# 407-power.net
KiCad netlist of a schematic drawn in Altium Designer
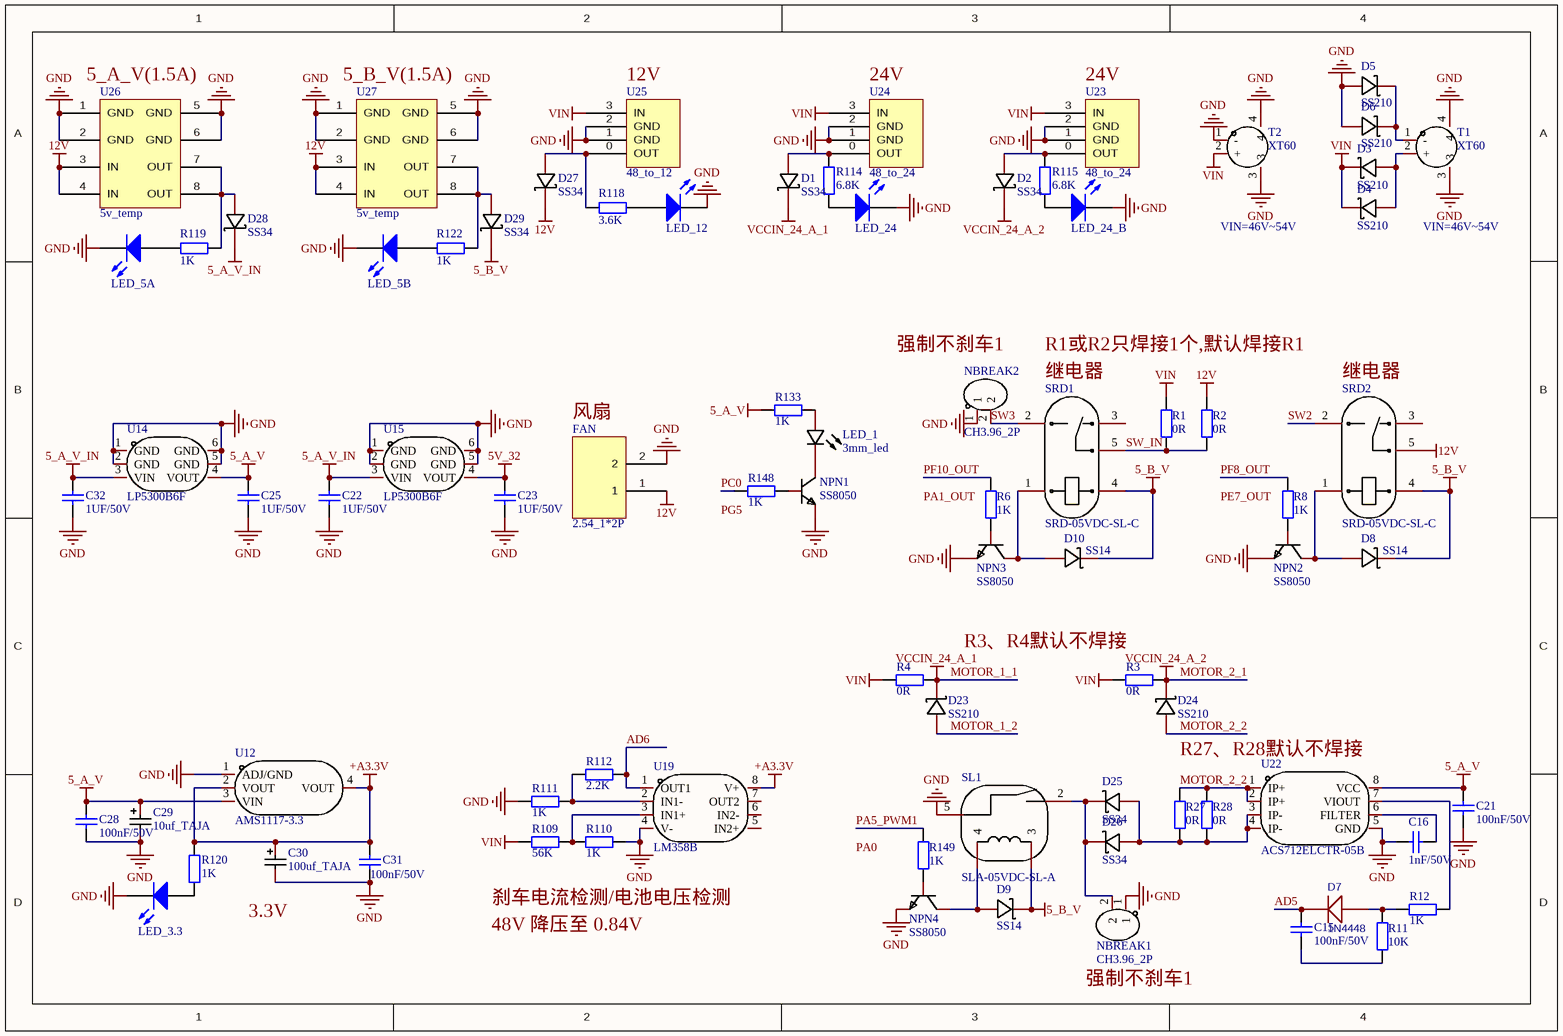
[diagram p0: 407-power.schdoc]

(export (version "E")
  (design (tool "Eeschema 10.0.6"))
  (components
    (comp (ref "C15")
      (value "100nF/50V")
      (description "Capacitor")
      (fields (field (name "PUBLISHER") "Altium Limited"))
      (libsource (lib "Miscellaneous Devices") (part "Cap"))
    )
    (comp (ref "C16")
      (value "1nF/50V")
      (description "Capacitor")
      (fields (field (name "PUBLISHER") "Altium Limited"))
      (libsource (lib "Miscellaneous Devices") (part "Cap"))
    )
    (comp (ref "C21")
      (value "100nF/50V")
      (description "Capacitor")
      (fields (field (name "PUBLISHER") "Altium Limited"))
      (libsource (lib "Miscellaneous Devices") (part "Cap"))
    )
    (comp (ref "C22")
      (value "1UF/50V")
      (description "Capacitor")
      (fields (field (name "PUBLISHER") "Altium Limited"))
      (libsource (lib "Miscellaneous Devices") (part "Cap"))
    )
    (comp (ref "C23")
      (value "1UF/50V")
      (description "Capacitor")
      (fields (field (name "PUBLISHER") "Altium Limited"))
      (libsource (lib "Miscellaneous Devices") (part "Cap"))
    )
    (comp (ref "C25")
      (value "1UF/50V")
      (description "Capacitor")
      (fields (field (name "PUBLISHER") "Altium Limited"))
      (libsource (lib "Miscellaneous Devices") (part "Cap"))
    )
    (comp (ref "C28")
      (value "100nF/50V")
      (description "Capacitor")
      (fields (field (name "PUBLISHER") "Altium Limited"))
      (libsource (lib "Miscellaneous Devices") (part "Cap"))
    )
    (comp (ref "C29")
      (value "10uf_TAJA")
      (footprint "10uf_TAJA")
      (libsource (lib "tianjin_2023") (part "10uf_TAJA"))
    )
    (comp (ref "C30")
      (value "100uf_TAJA")
      (footprint "100uf_TAJA")
      (libsource (lib "tianjin_2023") (part "100uf_TAJA"))
    )
    (comp (ref "C31")
      (value "100nF/50V")
      (description "Capacitor")
      (fields (field (name "PUBLISHER") "Altium Limited"))
      (libsource (lib "Miscellaneous Devices") (part "Cap"))
    )
    (comp (ref "C32")
      (value "1UF/50V")
      (description "Capacitor")
      (fields (field (name "PUBLISHER") "Altium Limited"))
      (libsource (lib "Miscellaneous Devices") (part "Cap"))
    )
    (comp (ref "D1") (value "SS34") (footprint "SS34") (libsource (lib "tianjin_2023") (part "SS34")))
    (comp (ref "D2") (value "SS34") (footprint "SS34") (libsource (lib "tianjin_2023") (part "SS34")))
    (comp (ref "D3") (value "SS210") (footprint "SS210") (libsource (lib "tianjin_2023") (part "SS210")))
    (comp (ref "D4") (value "SS210") (footprint "SS210") (libsource (lib "tianjin_2023") (part "SS210")))
    (comp (ref "D5") (value "SS210") (footprint "SS210") (libsource (lib "tianjin_2023") (part "SS210")))
    (comp (ref "D6") (value "SS210") (footprint "SS210") (libsource (lib "tianjin_2023") (part "SS210")))
    (comp (ref "D7")
      (value "1N4448")
      (fields (field (name "MANUFACTURER") "Diodes Inc") (field (name "MANUFACTURER PART") "1N4448HLP-7"))
      (libsource (lib "altium-import") (part "root_1_1N4448_"))
    )
    (comp (ref "D8") (value "SS14") (footprint "SS14") (libsource (lib "tianjin_2023") (part "SS14")))
    (comp (ref "D9") (value "SS14") (footprint "SS14") (libsource (lib "tianjin_2023") (part "SS14")))
    (comp (ref "D10") (value "SS14") (footprint "SS14") (libsource (lib "tianjin_2023") (part "SS14")))
    (comp (ref "D23") (value "SS210") (footprint "SS210") (libsource (lib "tianjin_2023") (part "SS210")))
    (comp (ref "D24") (value "SS210") (footprint "SS210") (libsource (lib "tianjin_2023") (part "SS210")))
    (comp (ref "D25") (value "SS34") (footprint "SS34") (libsource (lib "tianjin_2023") (part "SS34")))
    (comp (ref "D26") (value "SS34") (footprint "SS34") (libsource (lib "tianjin_2023") (part "SS34")))
    (comp (ref "D27") (value "SS34") (footprint "SS34") (libsource (lib "tianjin_2023") (part "SS34")))
    (comp (ref "D28") (value "SS34") (footprint "SS34") (libsource (lib "tianjin_2023") (part "SS34")))
    (comp (ref "D29") (value "SS34") (footprint "SS34") (libsource (lib "tianjin_2023") (part "SS34")))
    (comp (ref "FAN")
      (value "2.54_1*2P")
      (footprint "2.54_1*2P")
      (libsource (lib "tianjin_2023") (part "2.54_1*2P"))
    )
    (comp (ref "LED_1")
      (value "3mm_led")
      (footprint "3mm_led")
      (libsource (lib "tianjin_2023") (part "3mm_led"))
    )
    (comp (ref "LED_3.3")
      (value "LED")
      (footprint "LED")
      (description "发光二极管")
      (libsource (lib "0.3 - LED发光二极管-IR二极管_接收管-光耦") (part "LED"))
    )
    (comp (ref "LED_5A")
      (value "LED")
      (footprint "LED")
      (description "发光二极管")
      (libsource (lib "0.3 - LED发光二极管-IR二极管_接收管-光耦") (part "LED"))
    )
    (comp (ref "LED_5B")
      (value "LED")
      (footprint "LED")
      (description "发光二极管")
      (libsource (lib "0.3 - LED发光二极管-IR二极管_接收管-光耦") (part "LED"))
    )
    (comp (ref "LED_12")
      (value "LED")
      (footprint "LED")
      (description "发光二极管")
      (libsource (lib "0.3 - LED发光二极管-IR二极管_接收管-光耦") (part "LED"))
    )
    (comp (ref "LED_24")
      (value "LED")
      (footprint "LED")
      (description "发光二极管")
      (libsource (lib "0.3 - LED发光二极管-IR二极管_接收管-光耦") (part "LED"))
    )
    (comp (ref "LED_24_B")
      (value "LED")
      (footprint "LED")
      (description "发光二极管")
      (libsource (lib "0.3 - LED发光二极管-IR二极管_接收管-光耦") (part "LED"))
    )
    (comp (ref "NBREAK1")
      (value "CH3.96_2P")
      (footprint "CH3.96_2P")
      (libsource (lib "tianjin_2023") (part "CH3.96_2P"))
    )
    (comp (ref "NBREAK2") (value "CH3.96_2P") (libsource (lib "tianjin_2023") (part "CH3.96_2P")))
    (comp (ref "NPN1") (value "SS8050") (footprint "SS8050") (libsource (lib "tianjin_2023") (part "SS8050")))
    (comp (ref "NPN2") (value "SS8050") (footprint "SS8050") (libsource (lib "tianjin_2023") (part "SS8050")))
    (comp (ref "NPN3") (value "SS8050") (footprint "SS8050") (libsource (lib "tianjin_2023") (part "SS8050")))
    (comp (ref "NPN4") (value "SS8050") (footprint "SS8050") (libsource (lib "tianjin_2023") (part "SS8050")))
    (comp (ref "R1")
      (value "0R")
      (footprint "R1206_M")
      (description "Resistor")
      (fields (field (name "PUBLISHER") "Altium Limited"))
      (libsource (lib "") (part "Res2_3"))
    )
    (comp (ref "R2")
      (value "0R")
      (footprint "R1206_M")
      (description "Resistor")
      (fields (field (name "PUBLISHER") "Altium Limited"))
      (libsource (lib "") (part "Res2_1"))
    )
    (comp (ref "R3")
      (value "0R")
      (footprint "R1206_M")
      (description "Resistor")
      (fields (field (name "PUBLISHER") "Altium Limited"))
      (libsource (lib "MOS motor driving module ") (part "Res2"))
    )
    (comp (ref "R4")
      (value "0R")
      (footprint "R1206_M")
      (description "Resistor")
      (fields (field (name "PUBLISHER") "Altium Limited"))
      (libsource (lib "MOS motor driving module ") (part "Res2"))
    )
    (comp (ref "R6")
      (value "1K")
      (description "Resistor")
      (fields (field (name "PUBLISHER") "Altium Limited"))
      (libsource (lib "") (part "Res2_1"))
    )
    (comp (ref "R8")
      (value "1K")
      (description "Resistor")
      (fields (field (name "PUBLISHER") "Altium Limited"))
      (libsource (lib "") (part "Res2_1"))
    )
    (comp (ref "R11")
      (value "10K")
      (description "Resistor")
      (fields (field (name "PUBLISHER") "Altium Limited"))
      (libsource (lib "") (part "Res2_1"))
    )
    (comp (ref "R12")
      (value "1K")
      (description "Resistor")
      (fields (field (name "PUBLISHER") "Altium Limited"))
      (libsource (lib "") (part "Res2_2"))
    )
    (comp (ref "R27")
      (value "0R")
      (footprint "R1206_M")
      (description "Resistor")
      (fields (field (name "PUBLISHER") "Altium Limited"))
      (libsource (lib "") (part "Res2_3"))
    )
    (comp (ref "R28")
      (value "0R")
      (footprint "R1206_M")
      (description "Resistor")
      (fields (field (name "PUBLISHER") "Altium Limited"))
      (libsource (lib "") (part "Res2_3"))
    )
    (comp (ref "R109")
      (value "56K")
      (footprint "R0603_L")
      (description "Resistor")
      (fields (field (name "PUBLISHER") "Altium Limited"))
      (libsource (lib "MOS motor driving module ") (part "Res2"))
    )
    (comp (ref "R110")
      (value "1K")
      (footprint "R0603_L")
      (description "Resistor")
      (fields (field (name "PUBLISHER") "Altium Limited"))
      (libsource (lib "MOS motor driving module ") (part "Res2"))
    )
    (comp (ref "R111")
      (value "1K")
      (footprint "R0603_L")
      (description "Resistor")
      (fields (field (name "PUBLISHER") "Altium Limited"))
      (libsource (lib "MOS motor driving module ") (part "Res2"))
    )
    (comp (ref "R112")
      (value "2.2K")
      (footprint "R0603_L")
      (description "Resistor")
      (fields (field (name "PUBLISHER") "Altium Limited"))
      (libsource (lib "MOS motor driving module ") (part "Res2"))
    )
    (comp (ref "R114")
      (value "6.8K")
      (description "贴片电阻")
      (libsource (lib "0.1 - 电阻-电容-电感-晶振-晶体-磁珠-电位器-法拉电容-馈通电容") (part "R"))
    )
    (comp (ref "R115")
      (value "6.8K")
      (description "贴片电阻")
      (libsource (lib "0.1 - 电阻-电容-电感-晶振-晶体-磁珠-电位器-法拉电容-馈通电容") (part "R"))
    )
    (comp (ref "R118")
      (value "3.6K")
      (description "贴片电阻")
      (libsource (lib "0.1 - 电阻-电容-电感-晶振-晶体-磁珠-电位器-法拉电容-馈通电容") (part "R"))
    )
    (comp (ref "R119")
      (value "1K")
      (description "贴片电阻")
      (libsource (lib "0.1 - 电阻-电容-电感-晶振-晶体-磁珠-电位器-法拉电容-馈通电容") (part "R"))
    )
    (comp (ref "R120")
      (value "1K")
      (description "贴片电阻")
      (libsource (lib "0.1 - 电阻-电容-电感-晶振-晶体-磁珠-电位器-法拉电容-馈通电容") (part "R"))
    )
    (comp (ref "R122")
      (value "1K")
      (description "贴片电阻")
      (libsource (lib "0.1 - 电阻-电容-电感-晶振-晶体-磁珠-电位器-法拉电容-馈通电容") (part "R"))
    )
    (comp (ref "R133")
      (value "1K")
      (description "Resistor")
      (fields (field (name "PUBLISHER") "Altium Limited"))
      (libsource (lib "MOS motor driving module ") (part "Res2"))
    )
    (comp (ref "R148")
      (value "1K")
      (description "Resistor")
      (fields (field (name "PUBLISHER") "Altium Limited"))
      (libsource (lib "") (part "Res2_2"))
    )
    (comp (ref "R149")
      (value "1K")
      (description "Resistor")
      (fields (field (name "PUBLISHER") "Altium Limited"))
      (libsource (lib "") (part "Res2_1"))
    )
    (comp (ref "SL1")
      (value "SLA-05VDC-SL-A")
      (footprint "SLA-05VDC-SL-A")
      (libsource (lib "tianjin_2023") (part "SLA-05VDC-SL-A"))
    )
    (comp (ref "SRD1")
      (value "SRD-05VDC-SL-C")
      (footprint "SRD-05VDC-SL-C")
      (libsource (lib "tianjin_2023") (part "SRD-05VDC-SL-C"))
    )
    (comp (ref "SRD2")
      (value "SRD-05VDC-SL-C")
      (footprint "SRD-05VDC-SL-C")
      (libsource (lib "tianjin_2023") (part "SRD-05VDC-SL-C"))
    )
    (comp (ref "T1") (value "XT60") (libsource (lib "tianjin_2023") (part "XT60")))
    (comp (ref "T2") (value "XT60") (libsource (lib "tianjin_2023") (part "XT60")))
    (comp (ref "U12")
      (value "AMS1117-3.3")
      (footprint "AMS1117-3.3")
      (libsource (lib "tianjin_2023") (part "AMS1117-3.3"))
    )
    (comp (ref "U14")
      (value "LP5300B6F")
      (footprint "LP5300B6F")
      (libsource (lib "tianjin_2023") (part "LP5300B6F"))
    )
    (comp (ref "U15")
      (value "LP5300B6F")
      (footprint "LP5300B6F")
      (libsource (lib "tianjin_2023") (part "LP5300B6F"))
    )
    (comp (ref "U19") (value "LM358B") (footprint "LM358B") (libsource (lib "tianjin_2023") (part "LM358B")))
    (comp (ref "U22")
      (value "ACS712ELCTR-05B")
      (footprint "ACS712ELCTR-05B")
      (libsource (lib "tianjin_2023") (part "ACS712ELCTR-05B"))
    )
    (comp (ref "U23")
      (value "48_to_24")
      (footprint "48_to_24")
      (libsource (lib "tianjin_2023") (part "48_to_24"))
    )
    (comp (ref "U24")
      (value "48_to_24")
      (footprint "48_to_24")
      (libsource (lib "tianjin_2023") (part "48_to_24"))
    )
    (comp (ref "U25")
      (value "48_to_12")
      (footprint "48_to_12")
      (libsource (lib "tianjin_2023") (part "48_to_12"))
    )
    (comp (ref "U26")
      (value "5v_temp")
      (footprint "5v_temp")
      (libsource (lib "tianjin_2023") (part "5v_temp"))
    )
    (comp (ref "U27")
      (value "5v_temp")
      (footprint "5v_temp")
      (libsource (lib "tianjin_2023") (part "5v_temp"))
    )
  )
  (nets
    (net (code "1") (name "+A3.3V") (class "Default")
      (node (ref "C30") (pin "1") (pinfunction "1_1") (pintype "passive"))
      (node (ref "C31") (pin "1") (pinfunction "1_1") (pintype "passive"))
      (node (ref "R120") (pin "1") (pinfunction "1_1") (pintype "passive"))
      (node (ref "U12") (pin "2") (pinfunction "VOUT_2") (pintype "passive"))
      (node (ref "U12") (pin "4") (pinfunction "VOUT_4") (pintype "passive"))
      (node (ref "U19") (pin "8") (pinfunction "V+_8") (pintype "passive"))
    )
    (net (code "3") (name "/AD5") (class "Default")
      (node (ref "C15") (pin "1") (pinfunction "1_1") (pintype "passive"))
      (node (ref "D7") (pin "1") (pinfunction "K_1") (pintype "passive"))
    )
    (net (code "4") (name "/AD6") (class "Default")
      (node (ref "R112") (pin "1") (pinfunction "1_1") (pintype "passive"))
      (node (ref "U19") (pin "1") (pinfunction "OUT1_1") (pintype "passive"))
    )
    (net (code "5") (name "/MOTOR_1_2") (class "Default")
      (node (ref "D23") (pin "2") (pinfunction "A_2") (pintype "passive"))
    )
    (net (code "6") (name "/MOTOR_2_2") (class "Default")
      (node (ref "D24") (pin "2") (pinfunction "A_2") (pintype "passive"))
      (node (ref "R27") (pin "2") (pinfunction "2_2") (pintype "passive"))
      (node (ref "R28") (pin "2") (pinfunction "2_2") (pintype "passive"))
      (node (ref "U22") (pin "1") (pinfunction "IP+_1") (pintype "passive"))
      (node (ref "U22") (pin "2") (pinfunction "IP+_2") (pintype "passive"))
    )
    (net (code "9") (name "/PA5_PWM1") (class "Default")
      (node (ref "R149") (pin "1") (pinfunction "1_1") (pintype "passive"))
    )
    (net (code "10") (name "/PC0") (class "Default")
      (node (ref "R148") (pin "1") (pinfunction "1_1") (pintype "passive"))
    )
    (net (code "12") (name "/PF8_OUT") (class "Default")
      (node (ref "R8") (pin "1") (pinfunction "1_1") (pintype "passive"))
    )
    (net (code "13") (name "/PF10_OUT") (class "Default")
      (node (ref "R6") (pin "1") (pinfunction "1_1") (pintype "passive"))
    )
    (net (code "15") (name "/SW2") (class "Default")
      (node (ref "SRD2") (pin "2") (pinfunction "2_2") (pintype "passive"))
    )
    (net (code "16") (name "/SW3") (class "Default")
      (node (ref "NBREAK2") (pin "2") (pinfunction "2_2") (pintype "passive"))
      (node (ref "SRD1") (pin "2") (pinfunction "2_2") (pintype "passive"))
    )
    (net (code "17") (name "/SW_IN") (class "Default")
      (node (ref "R1") (pin "1") (pinfunction "1_1") (pintype "passive"))
      (node (ref "R2") (pin "2") (pinfunction "2_2") (pintype "passive"))
      (node (ref "SRD1") (pin "5") (pinfunction "5_5") (pintype "passive"))
    )
    (net (code "18") (name "5V_32") (class "Default")
      (node (ref "C23") (pin "2") (pinfunction "2_2") (pintype "passive"))
      (node (ref "U15") (pin "4") (pinfunction "VOUT_4") (pintype "passive"))
    )
    (net (code "19") (name "5_A_V") (class "Default")
      (node (ref "C21") (pin "2") (pinfunction "2_2") (pintype "passive"))
      (node (ref "C25") (pin "2") (pinfunction "2_2") (pintype "passive"))
      (node (ref "C28") (pin "1") (pinfunction "1_1") (pintype "passive"))
      (node (ref "C29") (pin "1") (pinfunction "1_1") (pintype "passive"))
      (node (ref "R133") (pin "2") (pinfunction "2_2") (pintype "passive"))
      (node (ref "U12") (pin "3") (pinfunction "VIN_3") (pintype "passive"))
      (node (ref "U14") (pin "4") (pinfunction "VOUT_4") (pintype "passive"))
      (node (ref "U22") (pin "8") (pinfunction "VCC_8") (pintype "passive"))
    )
    (net (code "20") (name "5_A_V_IN") (class "Default")
      (node (ref "C22") (pin "2") (pinfunction "2_2") (pintype "passive"))
      (node (ref "C32") (pin "2") (pinfunction "2_2") (pintype "passive"))
      (node (ref "D28") (pin "1") (pinfunction "K_1") (pintype "passive"))
      (node (ref "U14") (pin "3") (pinfunction "VIN_3") (pintype "passive"))
      (node (ref "U15") (pin "3") (pinfunction "VIN_3") (pintype "passive"))
    )
    (net (code "21") (name "5_B_V") (class "Default")
      (node (ref "D10") (pin "1") (pinfunction "K_1") (pintype "passive"))
      (node (ref "D29") (pin "1") (pinfunction "K_1") (pintype "passive"))
      (node (ref "D8") (pin "1") (pinfunction "K_1") (pintype "passive"))
      (node (ref "D9") (pin "1") (pinfunction "K_1") (pintype "passive"))
      (node (ref "SL1") (pin "3") (pinfunction "3_3") (pintype "passive"))
      (node (ref "SRD1") (pin "4") (pinfunction "4_4") (pintype "passive"))
      (node (ref "SRD2") (pin "4") (pinfunction "4_4") (pintype "passive"))
    )
    (net (code "22") (name "12V") (class "Default")
      (node (ref "D27") (pin "1") (pinfunction "K_1") (pintype "passive"))
      (node (ref "FAN") (pin "1") (pinfunction "1_1") (pintype "passive"))
      (node (ref "R2") (pin "1") (pinfunction "1_1") (pintype "passive"))
      (node (ref "SRD2") (pin "5") (pinfunction "5_5") (pintype "passive"))
      (node (ref "U26") (pin "3") (pinfunction "IN_3") (pintype "passive"))
      (node (ref "U26") (pin "4") (pinfunction "IN_4") (pintype "passive"))
      (node (ref "U27") (pin "3") (pinfunction "IN_3") (pintype "passive"))
      (node (ref "U27") (pin "4") (pinfunction "IN_4") (pintype "passive"))
    )
    (net (code "23") (name "GND") (class "Default")
      (node (ref "C16") (pin "2") (pinfunction "2_2") (pintype "passive"))
      (node (ref "C21") (pin "1") (pinfunction "1_1") (pintype "passive"))
      (node (ref "C22") (pin "1") (pinfunction "1_1") (pintype "passive"))
      (node (ref "C23") (pin "1") (pinfunction "1_1") (pintype "passive"))
      (node (ref "C25") (pin "1") (pinfunction "1_1") (pintype "passive"))
      (node (ref "C28") (pin "2") (pinfunction "2_2") (pintype "passive"))
      (node (ref "C29") (pin "2") (pinfunction "2_2") (pintype "passive"))
      (node (ref "C30") (pin "2") (pinfunction "2_2") (pintype "passive"))
      (node (ref "C31") (pin "2") (pinfunction "2_2") (pintype "passive"))
      (node (ref "C32") (pin "1") (pinfunction "1_1") (pintype "passive"))
      (node (ref "D5") (pin "2") (pinfunction "A_2") (pintype "passive"))
      (node (ref "D6") (pin "2") (pinfunction "A_2") (pintype "passive"))
      (node (ref "FAN") (pin "2") (pinfunction "2_2") (pintype "passive"))
      (node (ref "LED_12") (pin "2") (pinfunction "K_2") (pintype "passive"))
      (node (ref "LED_24") (pin "2") (pinfunction "K_2") (pintype "passive"))
      (node (ref "LED_24_B") (pin "2") (pinfunction "K_2") (pintype "passive"))
      (node (ref "LED_3.3") (pin "2") (pinfunction "K_2") (pintype "passive"))
      (node (ref "LED_5A") (pin "2") (pinfunction "K_2") (pintype "passive"))
      (node (ref "LED_5B") (pin "2") (pinfunction "K_2") (pintype "passive"))
      (node (ref "NBREAK1") (pin "1") (pinfunction "1_1") (pintype "passive"))
      (node (ref "NBREAK2") (pin "1") (pinfunction "1_1") (pintype "passive"))
      (node (ref "NPN1") (pin "2") (pinfunction "E_2") (pintype "passive"))
      (node (ref "NPN2") (pin "2") (pinfunction "E_2") (pintype "passive"))
      (node (ref "NPN3") (pin "2") (pinfunction "E_2") (pintype "passive"))
      (node (ref "NPN4") (pin "2") (pinfunction "E_2") (pintype "passive"))
      (node (ref "R110") (pin "1") (pinfunction "1_1") (pintype "passive"))
      (node (ref "R111") (pin "2") (pinfunction "2_2") (pintype "passive"))
      (node (ref "SL1") (pin "5") (pinfunction "5_5") (pintype "passive"))
      (node (ref "T1") (pin "3") (pinfunction "3_3") (pintype "passive"))
      (node (ref "T1") (pin "4") (pinfunction "4_4") (pintype "passive"))
      (node (ref "T2") (pin "1") (pinfunction "-_1") (pintype "passive"))
      (node (ref "T2") (pin "3") (pinfunction "3_3") (pintype "passive"))
      (node (ref "T2") (pin "4") (pinfunction "4_4") (pintype "passive"))
      (node (ref "U12") (pin "1") (pinfunction "ADJ/GND_1") (pintype "passive"))
      (node (ref "U14") (pin "1") (pinfunction "GND_1") (pintype "passive"))
      (node (ref "U14") (pin "2") (pinfunction "GND_2") (pintype "passive"))
      (node (ref "U14") (pin "5") (pinfunction "GND_5") (pintype "passive"))
      (node (ref "U14") (pin "6") (pinfunction "GND_6") (pintype "passive"))
      (node (ref "U15") (pin "1") (pinfunction "GND_1") (pintype "passive"))
      (node (ref "U15") (pin "2") (pinfunction "GND_2") (pintype "passive"))
      (node (ref "U15") (pin "5") (pinfunction "GND_5") (pintype "passive"))
      (node (ref "U15") (pin "6") (pinfunction "GND_6") (pintype "passive"))
      (node (ref "U19") (pin "4") (pinfunction "V-_4") (pintype "passive"))
      (node (ref "U22") (pin "5") (pinfunction "GND_5") (pintype "passive"))
      (node (ref "U23") (pin "1") (pinfunction "GND_1") (pintype "passive"))
      (node (ref "U23") (pin "2") (pinfunction "GND_2") (pintype "passive"))
      (node (ref "U24") (pin "1") (pinfunction "GND_1") (pintype "passive"))
      (node (ref "U24") (pin "2") (pinfunction "GND_2") (pintype "passive"))
      (node (ref "U25") (pin "1") (pinfunction "GND_1") (pintype "passive"))
      (node (ref "U25") (pin "2") (pinfunction "GND_2") (pintype "passive"))
      (node (ref "U26") (pin "1") (pinfunction "GND_1") (pintype "passive"))
      (node (ref "U26") (pin "2") (pinfunction "GND_2") (pintype "passive"))
      (node (ref "U26") (pin "5") (pinfunction "GND_5") (pintype "passive"))
      (node (ref "U26") (pin "6") (pinfunction "GND_6") (pintype "passive"))
      (node (ref "U27") (pin "1") (pinfunction "GND_1") (pintype "passive"))
      (node (ref "U27") (pin "2") (pinfunction "GND_2") (pintype "passive"))
      (node (ref "U27") (pin "5") (pinfunction "GND_5") (pintype "passive"))
      (node (ref "U27") (pin "6") (pinfunction "GND_6") (pintype "passive"))
    )
    (net (code "24") (name "Net-(C15-Pad2)") (class "Default")
      (node (ref "C15") (pin "2") (pinfunction "2_2") (pintype "passive"))
      (node (ref "R11") (pin "2") (pinfunction "2_2") (pintype "passive"))
    )
    (net (code "25") (name "Net-(D1-A)") (class "Default")
      (node (ref "D1") (pin "2") (pinfunction "A_2") (pintype "passive"))
      (node (ref "R114") (pin "1") (pinfunction "1_1") (pintype "passive"))
      (node (ref "U24") (pin "0") (pinfunction "OUT_0") (pintype "passive"))
    )
    (net (code "26") (name "Net-(D2-A)") (class "Default")
      (node (ref "D2") (pin "2") (pinfunction "A_2") (pintype "passive"))
      (node (ref "R115") (pin "1") (pinfunction "1_1") (pintype "passive"))
      (node (ref "U23") (pin "0") (pinfunction "OUT_0") (pintype "passive"))
    )
    (net (code "27") (name "Net-(D3-A)") (class "Default")
      (node (ref "D3") (pin "2") (pinfunction "A_2") (pintype "passive"))
      (node (ref "D4") (pin "2") (pinfunction "A_2") (pintype "passive"))
      (node (ref "T1") (pin "2") (pinfunction "+_2") (pintype "passive"))
    )
    (net (code "28") (name "Net-(D5-K)") (class "Default")
      (node (ref "D5") (pin "1") (pinfunction "K_1") (pintype "passive"))
      (node (ref "D6") (pin "1") (pinfunction "K_1") (pintype "passive"))
      (node (ref "T1") (pin "1") (pinfunction "-_1") (pintype "passive"))
    )
    (net (code "29") (name "Net-(D7-A)") (class "Default")
      (node (ref "D7") (pin "2") (pinfunction "A_2") (pintype "passive"))
      (node (ref "R11") (pin "1") (pinfunction "1_1") (pintype "passive"))
      (node (ref "R12") (pin "1") (pinfunction "1_1") (pintype "passive"))
    )
    (net (code "30") (name "Net-(D8-A)") (class "Default")
      (node (ref "D8") (pin "2") (pinfunction "A_2") (pintype "passive"))
      (node (ref "NPN2") (pin "3") (pinfunction "C_3") (pintype "passive"))
      (node (ref "SRD2") (pin "1") (pinfunction "1_1") (pintype "passive"))
    )
    (net (code "31") (name "Net-(D9-A)") (class "Default")
      (node (ref "D9") (pin "2") (pinfunction "A_2") (pintype "passive"))
      (node (ref "NPN4") (pin "3") (pinfunction "C_3") (pintype "passive"))
      (node (ref "SL1") (pin "4") (pinfunction "4_4") (pintype "passive"))
    )
    (net (code "32") (name "Net-(D10-A)") (class "Default")
      (node (ref "D10") (pin "2") (pinfunction "A_2") (pintype "passive"))
      (node (ref "NPN3") (pin "3") (pinfunction "C_3") (pintype "passive"))
      (node (ref "SRD1") (pin "1") (pinfunction "1_1") (pintype "passive"))
    )
    (net (code "33") (name "Net-(D25-A)") (class "Default")
      (node (ref "D25") (pin "2") (pinfunction "A_2") (pintype "passive"))
      (node (ref "D26") (pin "2") (pinfunction "A_2") (pintype "passive"))
      (node (ref "R27") (pin "1") (pinfunction "1_1") (pintype "passive"))
      (node (ref "R28") (pin "1") (pinfunction "1_1") (pintype "passive"))
      (node (ref "U22") (pin "3") (pinfunction "IP-_3") (pintype "passive"))
      (node (ref "U22") (pin "4") (pinfunction "IP-_4") (pintype "passive"))
    )
    (net (code "34") (name "Net-(D25-K)") (class "Default")
      (node (ref "D25") (pin "1") (pinfunction "K_1") (pintype "passive"))
      (node (ref "D26") (pin "1") (pinfunction "K_1") (pintype "passive"))
      (node (ref "NBREAK1") (pin "2") (pinfunction "2_2") (pintype "passive"))
      (node (ref "SL1") (pin "2") (pinfunction "2_2") (pintype "passive"))
    )
    (net (code "35") (name "Net-(D27-A)") (class "Default")
      (node (ref "D27") (pin "2") (pinfunction "A_2") (pintype "passive"))
      (node (ref "R118") (pin "1") (pinfunction "1_1") (pintype "passive"))
      (node (ref "U25") (pin "0") (pinfunction "OUT_0") (pintype "passive"))
    )
    (net (code "36") (name "Net-(D28-A)") (class "Default")
      (node (ref "D28") (pin "2") (pinfunction "A_2") (pintype "passive"))
      (node (ref "R119") (pin "1") (pinfunction "1_1") (pintype "passive"))
      (node (ref "U26") (pin "7") (pinfunction "OUT_7") (pintype "passive"))
      (node (ref "U26") (pin "8") (pinfunction "OUT_8") (pintype "passive"))
    )
    (net (code "37") (name "Net-(D29-A)") (class "Default")
      (node (ref "D29") (pin "2") (pinfunction "A_2") (pintype "passive"))
      (node (ref "R122") (pin "2") (pinfunction "2_2") (pintype "passive"))
      (node (ref "U27") (pin "7") (pinfunction "OUT_7") (pintype "passive"))
      (node (ref "U27") (pin "8") (pinfunction "OUT_8") (pintype "passive"))
    )
    (net (code "38") (name "Net-(LED_1-A)") (class "Default")
      (node (ref "LED_1") (pin "1") (pinfunction "A_1") (pintype "passive"))
      (node (ref "R133") (pin "1") (pinfunction "1_1") (pintype "passive"))
    )
    (net (code "39") (name "Net-(LED_1-K)") (class "Default")
      (node (ref "LED_1") (pin "2") (pinfunction "K_2") (pintype "passive"))
      (node (ref "NPN1") (pin "3") (pinfunction "C_3") (pintype "passive"))
    )
    (net (code "40") (name "Net-(LED_3.3-A)") (class "Default")
      (node (ref "LED_3.3") (pin "1") (pinfunction "A_1") (pintype "passive"))
      (node (ref "R120") (pin "2") (pinfunction "2_2") (pintype "passive"))
    )
    (net (code "41") (name "Net-(LED_5A-A)") (class "Default")
      (node (ref "LED_5A") (pin "1") (pinfunction "A_1") (pintype "passive"))
      (node (ref "R119") (pin "2") (pinfunction "2_2") (pintype "passive"))
    )
    (net (code "42") (name "Net-(LED_5B-A)") (class "Default")
      (node (ref "LED_5B") (pin "1") (pinfunction "A_1") (pintype "passive"))
      (node (ref "R122") (pin "1") (pinfunction "1_1") (pintype "passive"))
    )
    (net (code "43") (name "Net-(LED_12-A)") (class "Default")
      (node (ref "LED_12") (pin "1") (pinfunction "A_1") (pintype "passive"))
      (node (ref "R118") (pin "2") (pinfunction "2_2") (pintype "passive"))
    )
    (net (code "44") (name "Net-(LED_24-A)") (class "Default")
      (node (ref "LED_24") (pin "1") (pinfunction "A_1") (pintype "passive"))
      (node (ref "R114") (pin "2") (pinfunction "2_2") (pintype "passive"))
    )
    (net (code "45") (name "Net-(LED_24_B-A)") (class "Default")
      (node (ref "LED_24_B") (pin "1") (pinfunction "A_1") (pintype "passive"))
      (node (ref "R115") (pin "2") (pinfunction "2_2") (pintype "passive"))
    )
    (net (code "46") (name "Net-(NPN1-B)") (class "Default")
      (node (ref "NPN1") (pin "1") (pinfunction "B_1") (pintype "passive"))
      (node (ref "R148") (pin "2") (pinfunction "2_2") (pintype "passive"))
    )
    (net (code "47") (name "Net-(NPN2-B)") (class "Default")
      (node (ref "NPN2") (pin "1") (pinfunction "B_1") (pintype "passive"))
      (node (ref "R8") (pin "2") (pinfunction "2_2") (pintype "passive"))
    )
    (net (code "48") (name "Net-(NPN3-B)") (class "Default")
      (node (ref "NPN3") (pin "1") (pinfunction "B_1") (pintype "passive"))
      (node (ref "R6") (pin "2") (pinfunction "2_2") (pintype "passive"))
    )
    (net (code "49") (name "Net-(NPN4-B)") (class "Default")
      (node (ref "NPN4") (pin "1") (pinfunction "B_1") (pintype "passive"))
      (node (ref "R149") (pin "2") (pinfunction "2_2") (pintype "passive"))
    )
    (net (code "50") (name "Net-(U19-IN1+)") (class "Default")
      (node (ref "R109") (pin "1") (pinfunction "1_1") (pintype "passive"))
      (node (ref "R110") (pin "2") (pinfunction "2_2") (pintype "passive"))
      (node (ref "U19") (pin "3") (pinfunction "IN1+_3") (pintype "passive"))
    )
    (net (code "51") (name "Net-(U19-IN1-)") (class "Default")
      (node (ref "R111") (pin "1") (pinfunction "1_1") (pintype "passive"))
      (node (ref "R112") (pin "2") (pinfunction "2_2") (pintype "passive"))
      (node (ref "U19") (pin "2") (pinfunction "IN1-_2") (pintype "passive"))
    )
    (net (code "52") (name "Net-(U22-FILTER)") (class "Default")
      (node (ref "C16") (pin "1") (pinfunction "1_1") (pintype "passive"))
      (node (ref "U22") (pin "6") (pinfunction "FILTER_6") (pintype "passive"))
    )
    (net (code "53") (name "Net-(U22-VIOUT)") (class "Default")
      (node (ref "R12") (pin "2") (pinfunction "2_2") (pintype "passive"))
      (node (ref "U22") (pin "7") (pinfunction "VIOUT_7") (pintype "passive"))
    )
    (net (code "54") (name "VCCIN_24_A_1") (class "Default")
      (node (ref "D1") (pin "1") (pinfunction "K_1") (pintype "passive"))
      (node (ref "D23") (pin "1") (pinfunction "K_1") (pintype "passive"))
      (node (ref "R4") (pin "1") (pinfunction "1_1") (pintype "passive"))
    )
    (net (code "55") (name "VCCIN_24_A_2") (class "Default")
      (node (ref "D2") (pin "1") (pinfunction "K_1") (pintype "passive"))
      (node (ref "D24") (pin "1") (pinfunction "K_1") (pintype "passive"))
      (node (ref "R3") (pin "1") (pinfunction "1_1") (pintype "passive"))
    )
    (net (code "56") (name "VIN") (class "Default")
      (node (ref "D3") (pin "1") (pinfunction "K_1") (pintype "passive"))
      (node (ref "D4") (pin "1") (pinfunction "K_1") (pintype "passive"))
      (node (ref "R1") (pin "2") (pinfunction "2_2") (pintype "passive"))
      (node (ref "R109") (pin "2") (pinfunction "2_2") (pintype "passive"))
      (node (ref "R3") (pin "2") (pinfunction "2_2") (pintype "passive"))
      (node (ref "R4") (pin "2") (pinfunction "2_2") (pintype "passive"))
      (node (ref "T2") (pin "2") (pinfunction "+_2") (pintype "passive"))
      (node (ref "U23") (pin "3") (pinfunction "IN_3") (pintype "passive"))
      (node (ref "U24") (pin "3") (pinfunction "IN_3") (pintype "passive"))
      (node (ref "U25") (pin "3") (pinfunction "IN_3") (pintype "passive"))
    )
    (net (code "57") (name "unconnected-(SRD1-Pad3)") (class "Default")
      (node (ref "SRD1") (pin "3") (pinfunction "3_3") (pintype "passive"))
    )
    (net (code "58") (name "unconnected-(SRD2-Pad3)") (class "Default")
      (node (ref "SRD2") (pin "3") (pinfunction "3_3") (pintype "passive"))
    )
    (net (code "59") (name "unconnected-(U19-IN2+-Pad5)") (class "Default")
      (node (ref "U19") (pin "5") (pinfunction "IN2+_5") (pintype "passive"))
    )
    (net (code "60") (name "unconnected-(U19-IN2--Pad6)") (class "Default")
      (node (ref "U19") (pin "6") (pinfunction "IN2-_6") (pintype "passive"))
    )
    (net (code "61") (name "unconnected-(U19-OUT2-Pad7)") (class "Default")
      (node (ref "U19") (pin "7") (pinfunction "OUT2_7") (pintype "passive"))
    )
  )
)
